# ip_simple.net
KiCad netlist of a schematic drawn in EAGLE
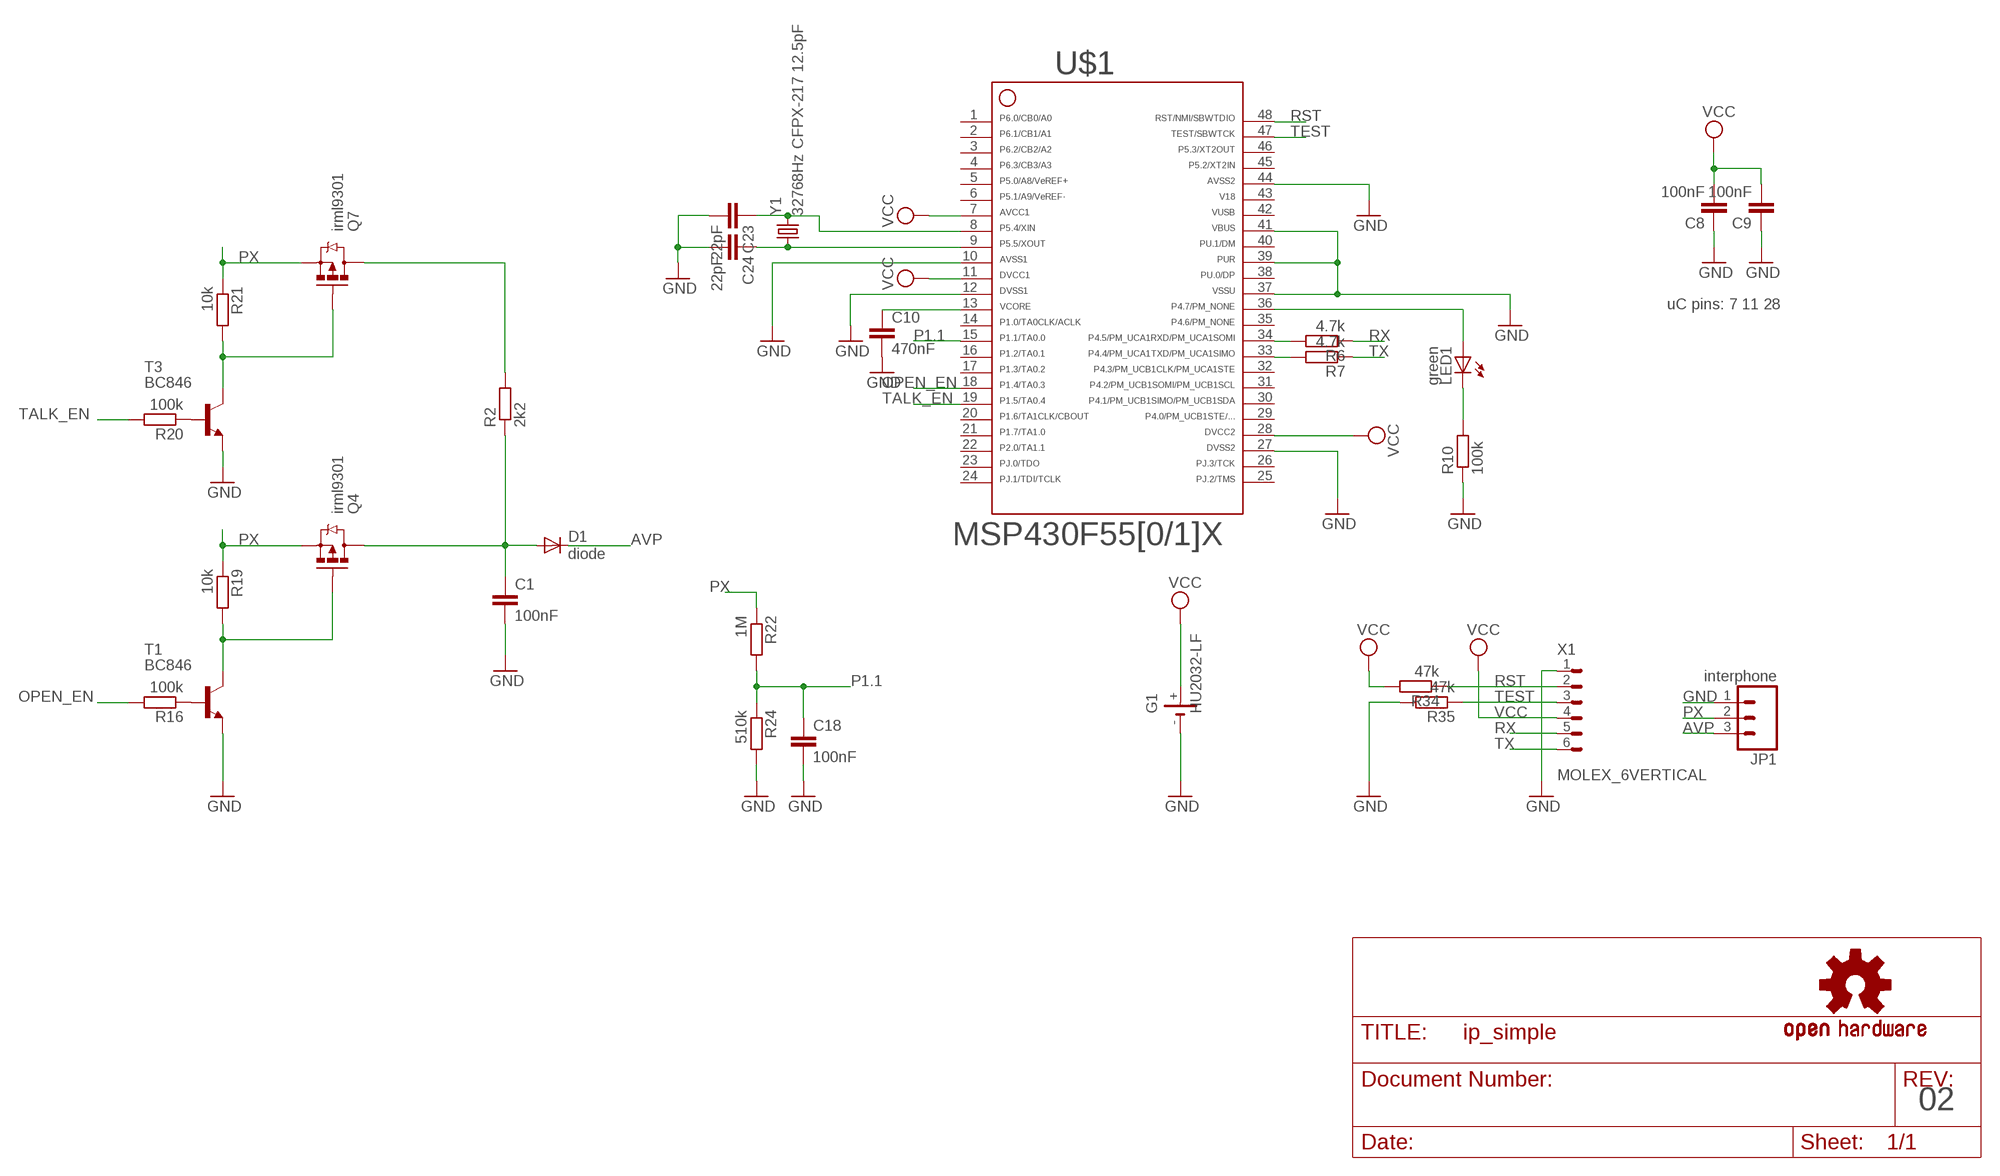
[diagram p0: schematic, sheet 1]

(export (version "E")
  (design (tool "Eeschema 10.0.6"))
  (components
    (comp (ref "C1")
      (value "100nF")
      (footprint "eagle-import:C0805")
      (libsource (lib "eagle-import") (part "C-EUC0805"))
    )
    (comp (ref "C8")
      (value "100nF")
      (footprint "eagle-import:C0805")
      (libsource (lib "eagle-import") (part "C-EUC0805"))
    )
    (comp (ref "C9")
      (value "100nF")
      (footprint "eagle-import:C0805")
      (libsource (lib "eagle-import") (part "C-EUC0805"))
    )
    (comp (ref "C10")
      (value "470nF")
      (footprint "eagle-import:C0805")
      (libsource (lib "eagle-import") (part "C-EUC0805"))
    )
    (comp (ref "C18")
      (value "100nF")
      (footprint "eagle-import:C0805")
      (libsource (lib "eagle-import") (part "C-EUC0805"))
    )
    (comp (ref "C23")
      (value "22pF")
      (footprint "eagle-import:C0805")
      (libsource (lib "eagle-import") (part "C-EUC0805"))
    )
    (comp (ref "C24")
      (value "22pF")
      (footprint "eagle-import:C0805")
      (libsource (lib "eagle-import") (part "C-EUC0805"))
    )
    (comp (ref "D1")
      (value "diode")
      (footprint "eagle-import:SMA-DIODE")
      (libsource (lib "eagle-import") (part "DIODESMA"))
    )
    (comp (ref "G1")
      (value "HU2032-LF")
      (footprint "eagle-import:HU2032-LF")
      (libsource (lib "eagle-import") (part "HU2032-LF"))
    )
    (comp (ref "JP1")
      (value "interphone")
      (footprint "eagle-import:1X03")
      (libsource (lib "eagle-import") (part "M03PTH"))
    )
    (comp (ref "LED1")
      (value "green")
      (footprint "eagle-import:CHIP-LED0805")
      (libsource (lib "eagle-import") (part "LEDCHIP-LED0805"))
    )
    (comp (ref "Q4")
      (value "irml9301")
      (footprint "eagle-import:SOT23-3_POWER")
      (libsource (lib "eagle-import") (part "MOSFET-PCHANNELSMD_POWER"))
    )
    (comp (ref "Q7")
      (value "irml9301")
      (footprint "eagle-import:SOT23-3_POWER")
      (libsource (lib "eagle-import") (part "MOSFET-PCHANNELSMD_POWER"))
    )
    (comp (ref "R2")
      (value "2k2")
      (footprint "eagle-import:R0805W")
      (libsource (lib "eagle-import") (part "R-EU_R0805W"))
    )
    (comp (ref "R6")
      (value "4.7k")
      (footprint "eagle-import:R0805W")
      (libsource (lib "eagle-import") (part "R-EU_R0805W"))
    )
    (comp (ref "R7")
      (value "4.7k")
      (footprint "eagle-import:R0805W")
      (libsource (lib "eagle-import") (part "R-EU_R0805W"))
    )
    (comp (ref "R10")
      (value "100k")
      (footprint "eagle-import:R0805W")
      (libsource (lib "eagle-import") (part "R-EU_R0805W"))
    )
    (comp (ref "R16")
      (value "100k")
      (footprint "eagle-import:R0805W")
      (libsource (lib "eagle-import") (part "R-EU_R0805W"))
    )
    (comp (ref "R19")
      (value "10k")
      (footprint "eagle-import:R0805W")
      (libsource (lib "eagle-import") (part "R-EU_R0805W"))
    )
    (comp (ref "R20")
      (value "100k")
      (footprint "eagle-import:R0805W")
      (libsource (lib "eagle-import") (part "R-EU_R0805W"))
    )
    (comp (ref "R21")
      (value "10k")
      (footprint "eagle-import:R0805W")
      (libsource (lib "eagle-import") (part "R-EU_R0805W"))
    )
    (comp (ref "R22")
      (value "1M")
      (footprint "eagle-import:R0805W")
      (libsource (lib "eagle-import") (part "R-EU_R0805W"))
    )
    (comp (ref "R24")
      (value "510k")
      (footprint "eagle-import:R0805W")
      (libsource (lib "eagle-import") (part "R-EU_R0805W"))
    )
    (comp (ref "R34")
      (value "47k")
      (footprint "eagle-import:R0805W")
      (libsource (lib "eagle-import") (part "R-EU_R0805W"))
    )
    (comp (ref "R35")
      (value "47k")
      (footprint "eagle-import:R0805W")
      (libsource (lib "eagle-import") (part "R-EU_R0805W"))
    )
    (comp (ref "T1")
      (value "BC846")
      (footprint "eagle-import:SOT23")
      (libsource (lib "eagle-import") (part "BC846"))
    )
    (comp (ref "T3")
      (value "BC846")
      (footprint "eagle-import:SOT23")
      (libsource (lib "eagle-import") (part "BC846"))
    )
    (comp (ref "U$1")
      (value "F55[0/1]X---PT48")
      (footprint "eagle-import:PT48")
      (libsource (lib "eagle-import") (part "F55[0/1]X---PT48"))
    )
    (comp (ref "U$7")
      (value "OSHW-LOGOM")
      (footprint "eagle-import:OSHW-LOGO-M")
      (libsource (lib "eagle-import") (part "OSHW-LOGOM"))
    )
    (comp (ref "X1")
      (value "MOLEX_6VERTICAL")
      (footprint "eagle-import:0530470610")
      (libsource (lib "eagle-import") (part "MOLEX_6VERTICAL"))
    )
    (comp (ref "Y1")
      (value "32768Hz CFPX-217 12.5pF")
      (footprint "eagle-import:CRYSTAL-SMD-3.2X1.5")
      (libsource (lib "eagle-import") (part "CRYSTAL3.2X1.5"))
    )
  )
  (nets
    (net (code "1") (name "/42") (class "Default")
      (node (ref "U$1") (pin "42") (pinfunction "42_42") (pintype "power_in"))
    )
    (net (code "2") (name "/43") (class "Default")
      (node (ref "U$1") (pin "43") (pinfunction "43_43") (pintype "power_in"))
    )
    (net (code "3") (name "/46") (class "Default")
      (node (ref "U$1") (pin "46") (pinfunction "46_46") (pintype "power_in"))
    )
    (net (code "4") (name "/AVP") (class "Default")
      (node (ref "D1") (pin "C") (pinfunction "C_C") (pintype "passive"))
      (node (ref "JP1") (pin "3") (pinfunction "3_3") (pintype "passive"))
    )
    (net (code "5") (name "/OPEN_EN") (class "Default")
      (node (ref "R16") (pin "2") (pinfunction "2_2") (pintype "passive"))
      (node (ref "U$1") (pin "18") (pinfunction "18_18") (pintype "bidirectional"))
    )
    (net (code "6") (name "/P1.1") (class "Default")
      (node (ref "C18") (pin "1") (pinfunction "1_1") (pintype "passive"))
      (node (ref "R22") (pin "2") (pinfunction "2_2") (pintype "passive"))
      (node (ref "R24") (pin "1") (pinfunction "1_1") (pintype "passive"))
      (node (ref "U$1") (pin "15") (pinfunction "15_15") (pintype "bidirectional"))
    )
    (net (code "7") (name "/PX") (class "Default")
      (node (ref "JP1") (pin "2") (pinfunction "2_2") (pintype "passive"))
      (node (ref "Q4") (pin "2") (pinfunction "S_2") (pintype "passive"))
      (node (ref "Q7") (pin "2") (pinfunction "S_2") (pintype "passive"))
      (node (ref "R19") (pin "1") (pinfunction "1_1") (pintype "passive"))
      (node (ref "R21") (pin "1") (pinfunction "1_1") (pintype "passive"))
      (node (ref "R22") (pin "1") (pinfunction "1_1") (pintype "passive"))
    )
    (net (code "8") (name "/RST") (class "Default")
      (node (ref "R34") (pin "1") (pinfunction "1_1") (pintype "passive"))
      (node (ref "U$1") (pin "48") (pinfunction "48_48") (pintype "bidirectional"))
      (node (ref "X1") (pin "2") (pinfunction "2_2") (pintype "passive"))
    )
    (net (code "9") (name "/RX") (class "Default")
      (node (ref "R6") (pin "1") (pinfunction "1_1") (pintype "passive"))
      (node (ref "X1") (pin "5") (pinfunction "5_5") (pintype "passive"))
    )
    (net (code "10") (name "/TALK_EN") (class "Default")
      (node (ref "R20") (pin "2") (pinfunction "2_2") (pintype "passive"))
      (node (ref "U$1") (pin "19") (pinfunction "19_19") (pintype "bidirectional"))
    )
    (net (code "11") (name "/TEST") (class "Default")
      (node (ref "R35") (pin "1") (pinfunction "1_1") (pintype "passive"))
      (node (ref "U$1") (pin "47") (pinfunction "47_47") (pintype "input"))
      (node (ref "X1") (pin "3") (pinfunction "3_3") (pintype "passive"))
    )
    (net (code "12") (name "/TX") (class "Default")
      (node (ref "R7") (pin "1") (pinfunction "1_1") (pintype "passive"))
      (node (ref "X1") (pin "6") (pinfunction "6_6") (pintype "passive"))
    )
    (net (code "13") (name "GND") (class "Default")
      (node (ref "C1") (pin "2") (pinfunction "2_2") (pintype "passive"))
      (node (ref "C10") (pin "2") (pinfunction "2_2") (pintype "passive"))
      (node (ref "C18") (pin "2") (pinfunction "2_2") (pintype "passive"))
      (node (ref "C23") (pin "2") (pinfunction "2_2") (pintype "passive"))
      (node (ref "C24") (pin "2") (pinfunction "2_2") (pintype "passive"))
      (node (ref "C8") (pin "1") (pinfunction "1_1") (pintype "passive"))
      (node (ref "C9") (pin "1") (pinfunction "1_1") (pintype "passive"))
      (node (ref "G1") (pin "-") (pinfunction "-_-") (pintype "passive"))
      (node (ref "JP1") (pin "1") (pinfunction "1_1") (pintype "passive"))
      (node (ref "R10") (pin "1") (pinfunction "1_1") (pintype "passive"))
      (node (ref "R24") (pin "2") (pinfunction "2_2") (pintype "passive"))
      (node (ref "R35") (pin "2") (pinfunction "2_2") (pintype "passive"))
      (node (ref "T1") (pin "2") (pinfunction "E_2") (pintype "passive"))
      (node (ref "T3") (pin "2") (pinfunction "E_2") (pintype "passive"))
      (node (ref "U$1") (pin "10") (pinfunction "10_10") (pintype "power_in"))
      (node (ref "U$1") (pin "12") (pinfunction "12_12") (pintype "power_in"))
      (node (ref "U$1") (pin "27") (pinfunction "27_27") (pintype "power_in"))
      (node (ref "U$1") (pin "37") (pinfunction "37_37") (pintype "power_in"))
      (node (ref "U$1") (pin "39") (pinfunction "39_39") (pintype "bidirectional"))
      (node (ref "U$1") (pin "41") (pinfunction "41_41") (pintype "power_in"))
      (node (ref "U$1") (pin "44") (pinfunction "44_44") (pintype "power_in"))
      (node (ref "X1") (pin "1") (pinfunction "1_1") (pintype "passive"))
    )
    (net (code "14") (name "Net-(C10-Pad1)") (class "Default")
      (node (ref "C10") (pin "1") (pinfunction "1_1") (pintype "passive"))
      (node (ref "U$1") (pin "13") (pinfunction "13_13") (pintype "power_in"))
    )
    (net (code "15") (name "Net-(LED1-PadA)") (class "Default")
      (node (ref "LED1") (pin "A") (pinfunction "A_A") (pintype "passive"))
      (node (ref "U$1") (pin "36") (pinfunction "36_36") (pintype "bidirectional"))
    )
    (net (code "16") (name "Net-(LED1-PadC)") (class "Default")
      (node (ref "LED1") (pin "C") (pinfunction "C_C") (pintype "passive"))
      (node (ref "R10") (pin "2") (pinfunction "2_2") (pintype "passive"))
    )
    (net (code "17") (name "Net-(Q4-D)") (class "Default")
      (node (ref "C1") (pin "1") (pinfunction "1_1") (pintype "passive"))
      (node (ref "D1") (pin "A") (pinfunction "A_A") (pintype "passive"))
      (node (ref "Q4") (pin "3") (pinfunction "D_3") (pintype "passive"))
      (node (ref "R2") (pin "1") (pinfunction "1_1") (pintype "passive"))
    )
    (net (code "18") (name "Net-(Q4-G)") (class "Default")
      (node (ref "Q4") (pin "1") (pinfunction "G_1") (pintype "passive"))
      (node (ref "R19") (pin "2") (pinfunction "2_2") (pintype "passive"))
      (node (ref "T1") (pin "3") (pinfunction "C_3") (pintype "passive"))
    )
    (net (code "19") (name "Net-(Q7-D)") (class "Default")
      (node (ref "Q7") (pin "3") (pinfunction "D_3") (pintype "passive"))
      (node (ref "R2") (pin "2") (pinfunction "2_2") (pintype "passive"))
    )
    (net (code "20") (name "Net-(Q7-G)") (class "Default")
      (node (ref "Q7") (pin "1") (pinfunction "G_1") (pintype "passive"))
      (node (ref "R21") (pin "2") (pinfunction "2_2") (pintype "passive"))
      (node (ref "T3") (pin "3") (pinfunction "C_3") (pintype "passive"))
    )
    (net (code "21") (name "Net-(R6-Pad2)") (class "Default")
      (node (ref "R6") (pin "2") (pinfunction "2_2") (pintype "passive"))
      (node (ref "U$1") (pin "34") (pinfunction "34_34") (pintype "bidirectional"))
    )
    (net (code "22") (name "Net-(R7-Pad2)") (class "Default")
      (node (ref "R7") (pin "2") (pinfunction "2_2") (pintype "passive"))
      (node (ref "U$1") (pin "33") (pinfunction "33_33") (pintype "bidirectional"))
    )
    (net (code "23") (name "Net-(T1-B)") (class "Default")
      (node (ref "R16") (pin "1") (pinfunction "1_1") (pintype "passive"))
      (node (ref "T1") (pin "1") (pinfunction "B_1") (pintype "passive"))
    )
    (net (code "24") (name "Net-(T3-B)") (class "Default")
      (node (ref "R20") (pin "1") (pinfunction "1_1") (pintype "passive"))
      (node (ref "T3") (pin "1") (pinfunction "B_1") (pintype "passive"))
    )
    (net (code "25") (name "Net-(Y1-1)") (class "Default")
      (node (ref "C24") (pin "1") (pinfunction "1_1") (pintype "passive"))
      (node (ref "U$1") (pin "9") (pinfunction "9_9") (pintype "bidirectional"))
      (node (ref "Y1") (pin "P$1") (pinfunction "1_P$1") (pintype "passive"))
    )
    (net (code "26") (name "Net-(Y1-2)") (class "Default")
      (node (ref "C23") (pin "1") (pinfunction "1_1") (pintype "passive"))
      (node (ref "U$1") (pin "8") (pinfunction "8_8") (pintype "bidirectional"))
      (node (ref "Y1") (pin "P$2") (pinfunction "2_P$2") (pintype "passive"))
    )
    (net (code "27") (name "VCC") (class "Default")
      (node (ref "C8") (pin "2") (pinfunction "2_2") (pintype "passive"))
      (node (ref "C9") (pin "2") (pinfunction "2_2") (pintype "passive"))
      (node (ref "G1") (pin "+") (pinfunction "+_+") (pintype "passive"))
      (node (ref "R34") (pin "2") (pinfunction "2_2") (pintype "passive"))
      (node (ref "U$1") (pin "11") (pinfunction "11_11") (pintype "power_in"))
      (node (ref "U$1") (pin "28") (pinfunction "28_28") (pintype "power_in"))
      (node (ref "U$1") (pin "7") (pinfunction "7_7") (pintype "power_in"))
      (node (ref "X1") (pin "4") (pinfunction "4_4") (pintype "passive"))
    )
    (net (code "28") (name "unconnected-(G1-+-Pad+@1)") (class "Default")
      (node (ref "G1") (pin "+@1") (pinfunction "+_+@1") (pintype "passive"))
    )
    (net (code "29") (name "unconnected-(U$1-Pad1)") (class "Default")
      (node (ref "U$1") (pin "1") (pinfunction "1_1") (pintype "bidirectional"))
    )
    (net (code "30") (name "unconnected-(U$1-Pad2)") (class "Default")
      (node (ref "U$1") (pin "2") (pinfunction "2_2") (pintype "bidirectional"))
    )
    (net (code "31") (name "unconnected-(U$1-Pad3)") (class "Default")
      (node (ref "U$1") (pin "3") (pinfunction "3_3") (pintype "bidirectional"))
    )
    (net (code "32") (name "unconnected-(U$1-Pad4)") (class "Default")
      (node (ref "U$1") (pin "4") (pinfunction "4_4") (pintype "bidirectional"))
    )
    (net (code "33") (name "unconnected-(U$1-Pad5)") (class "Default")
      (node (ref "U$1") (pin "5") (pinfunction "5_5") (pintype "bidirectional"))
    )
    (net (code "34") (name "unconnected-(U$1-Pad6)") (class "Default")
      (node (ref "U$1") (pin "6") (pinfunction "6_6") (pintype "bidirectional"))
    )
    (net (code "35") (name "unconnected-(U$1-Pad14)") (class "Default")
      (node (ref "U$1") (pin "14") (pinfunction "14_14") (pintype "bidirectional"))
    )
    (net (code "36") (name "unconnected-(U$1-Pad16)") (class "Default")
      (node (ref "U$1") (pin "16") (pinfunction "16_16") (pintype "bidirectional"))
    )
    (net (code "37") (name "unconnected-(U$1-Pad17)") (class "Default")
      (node (ref "U$1") (pin "17") (pinfunction "17_17") (pintype "bidirectional"))
    )
    (net (code "38") (name "unconnected-(U$1-Pad20)") (class "Default")
      (node (ref "U$1") (pin "20") (pinfunction "20_20") (pintype "bidirectional"))
    )
    (net (code "39") (name "unconnected-(U$1-Pad21)") (class "Default")
      (node (ref "U$1") (pin "21") (pinfunction "21_21") (pintype "bidirectional"))
    )
    (net (code "40") (name "unconnected-(U$1-Pad22)") (class "Default")
      (node (ref "U$1") (pin "22") (pinfunction "22_22") (pintype "bidirectional"))
    )
    (net (code "41") (name "unconnected-(U$1-Pad23)") (class "Default")
      (node (ref "U$1") (pin "23") (pinfunction "23_23") (pintype "bidirectional"))
    )
    (net (code "42") (name "unconnected-(U$1-Pad24)") (class "Default")
      (node (ref "U$1") (pin "24") (pinfunction "24_24") (pintype "bidirectional"))
    )
    (net (code "43") (name "unconnected-(U$1-Pad25)") (class "Default")
      (node (ref "U$1") (pin "25") (pinfunction "25_25") (pintype "bidirectional"))
    )
    (net (code "44") (name "unconnected-(U$1-Pad26)") (class "Default")
      (node (ref "U$1") (pin "26") (pinfunction "26_26") (pintype "bidirectional"))
    )
    (net (code "45") (name "unconnected-(U$1-Pad29)") (class "Default")
      (node (ref "U$1") (pin "29") (pinfunction "29_29") (pintype "bidirectional"))
    )
    (net (code "46") (name "unconnected-(U$1-Pad30)") (class "Default")
      (node (ref "U$1") (pin "30") (pinfunction "30_30") (pintype "bidirectional"))
    )
    (net (code "47") (name "unconnected-(U$1-Pad31)") (class "Default")
      (node (ref "U$1") (pin "31") (pinfunction "31_31") (pintype "bidirectional"))
    )
    (net (code "48") (name "unconnected-(U$1-Pad32)") (class "Default")
      (node (ref "U$1") (pin "32") (pinfunction "32_32") (pintype "bidirectional"))
    )
    (net (code "49") (name "unconnected-(U$1-Pad35)") (class "Default")
      (node (ref "U$1") (pin "35") (pinfunction "35_35") (pintype "bidirectional"))
    )
    (net (code "50") (name "unconnected-(U$1-Pad38)") (class "Default")
      (node (ref "U$1") (pin "38") (pinfunction "38_38") (pintype "bidirectional"))
    )
    (net (code "51") (name "unconnected-(U$1-Pad40)") (class "Default")
      (node (ref "U$1") (pin "40") (pinfunction "40_40") (pintype "bidirectional"))
    )
    (net (code "52") (name "unconnected-(U$1-Pad45)") (class "Default")
      (node (ref "U$1") (pin "45") (pinfunction "45_45") (pintype "bidirectional"))
    )
  )
)
